# RGB_LED_Shett.net
KiCad netlist of a schematic drawn in Altium Designer
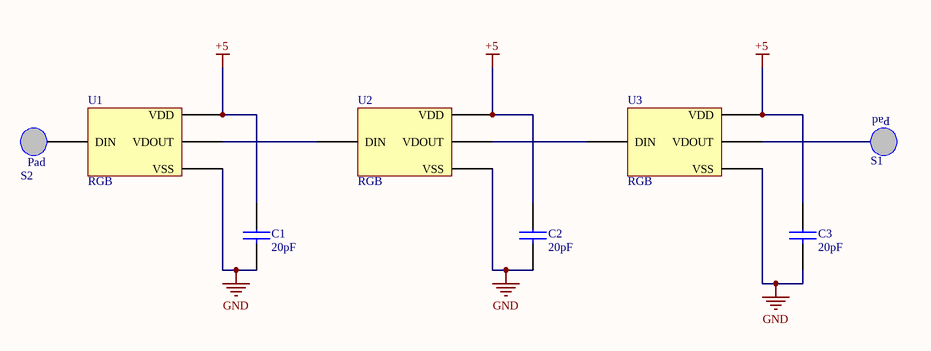
[diagram p0: RGB LED Shett.SchDoc]

(export (version "E")
  (design (tool "Eeschema 10.0.6"))
  (components
    (comp (ref "C1")
      (value "CL10C200JB8NNNC")
      (footprint "CAP_0603")
      (description "CAP CER 20pF %5 0603 SMD")
      (fields
        (field (name "MANUFACTURER") "Samsung")
        (field (name "TOLERANCE") "5%")
        (field (name "CAPACITANCE") "20pF")
        (field (name "DESIGNED BY") "BERK")
      )
      (libsource (lib "Integrated_Library01") (part "CAP CER 20pF 0603"))
    )
    (comp (ref "C2")
      (value "CL10C200JB8NNNC")
      (footprint "CAP_0603")
      (description "CAP CER 20pF %5 0603 SMD")
      (fields
        (field (name "MANUFACTURER") "Samsung")
        (field (name "TOLERANCE") "5%")
        (field (name "CAPACITANCE") "20pF")
        (field (name "DESIGNED BY") "BERK")
      )
      (libsource (lib "Integrated_Library01") (part "CAP CER 20pF 0603"))
    )
    (comp (ref "C3")
      (value "CL10C200JB8NNNC")
      (footprint "CAP_0603")
      (description "CAP CER 20pF %5 0603 SMD")
      (fields
        (field (name "MANUFACTURER") "Samsung")
        (field (name "TOLERANCE") "5%")
        (field (name "CAPACITANCE") "20pF")
        (field (name "DESIGNED BY") "BERK")
      )
      (libsource (lib "Integrated_Library01") (part "CAP CER 20pF 0603"))
    )
    (comp (ref "S1")
      (value "RGBsolderpad")
      (footprint "Solderpad0")
      (description "SOLDER PAD")
      (libsource (lib "Integrated_Library01") (part "RGBsolderpad"))
    )
    (comp (ref "S2")
      (value "RGBsolderpad")
      (footprint "Solderpad0")
      (description "SOLDER PAD")
      (libsource (lib "Integrated_Library01") (part "RGBsolderpad"))
    )
    (comp (ref "U1")
      (value "RGB")
      (footprint "RGB LED 1655")
      (description "Neopixel 5050 RGB LED with Integrated Driver Chip - 10 Pack")
      (fields
        (field (name "MANUFACTURER") "Adafruit Industries")
        (field (name "MANUFACTURER PART NUMBER") "1655")
      )
      (libsource (lib "Integrated_Library01") (part "RGB LED 1655"))
    )
    (comp (ref "U2")
      (value "RGB")
      (footprint "RGB LED 1655")
      (description "Neopixel 5050 RGB LED with Integrated Driver Chip - 10 Pack")
      (fields
        (field (name "MANUFACTURER") "Adafruit Industries")
        (field (name "MANUFACTURER PART NUMBER") "1655")
      )
      (libsource (lib "Integrated_Library01") (part "RGB LED 1655"))
    )
    (comp (ref "U3")
      (value "RGB")
      (footprint "RGB LED 1655")
      (description "Neopixel 5050 RGB LED with Integrated Driver Chip - 10 Pack")
      (fields
        (field (name "MANUFACTURER") "Adafruit Industries")
        (field (name "MANUFACTURER PART NUMBER") "1655")
      )
      (libsource (lib "Integrated_Library01") (part "RGB LED 1655"))
    )
  )
  (nets
    (net (code "1") (name "+5") (class "Default")
      (node (ref "C1") (pin "1") (pinfunction "1_1") (pintype "passive"))
      (node (ref "C2") (pin "1") (pinfunction "1_1") (pintype "passive"))
      (node (ref "C3") (pin "1") (pinfunction "1_1") (pintype "passive"))
      (node (ref "U1") (pin "2") (pinfunction "VDD_2") (pintype "passive"))
      (node (ref "U2") (pin "2") (pinfunction "VDD_2") (pintype "passive"))
      (node (ref "U3") (pin "2") (pinfunction "VDD_2") (pintype "passive"))
    )
    (net (code "2") (name "GND") (class "Default")
      (node (ref "C1") (pin "2") (pinfunction "2_2") (pintype "passive"))
      (node (ref "C2") (pin "2") (pinfunction "2_2") (pintype "passive"))
      (node (ref "C3") (pin "2") (pinfunction "2_2") (pintype "passive"))
      (node (ref "U1") (pin "4") (pinfunction "VSS_4") (pintype "passive"))
      (node (ref "U2") (pin "4") (pinfunction "VSS_4") (pintype "passive"))
      (node (ref "U3") (pin "4") (pinfunction "VSS_4") (pintype "passive"))
    )
    (net (code "3") (name "Net-(U1-DIN)") (class "Default")
      (node (ref "S2") (pin "1") (pintype "passive"))
      (node (ref "U1") (pin "1") (pinfunction "DIN_1") (pintype "passive"))
    )
    (net (code "4") (name "Net-(U1-VDOUT)") (class "Default")
      (node (ref "U1") (pin "3") (pinfunction "VDOUT_3") (pintype "passive"))
      (node (ref "U2") (pin "1") (pinfunction "DIN_1") (pintype "passive"))
    )
    (net (code "5") (name "Net-(U2-VDOUT)") (class "Default")
      (node (ref "U2") (pin "3") (pinfunction "VDOUT_3") (pintype "passive"))
      (node (ref "U3") (pin "1") (pinfunction "DIN_1") (pintype "passive"))
    )
    (net (code "6") (name "Net-(U3-VDOUT)") (class "Default")
      (node (ref "S1") (pin "1") (pintype "passive"))
      (node (ref "U3") (pin "3") (pinfunction "VDOUT_3") (pintype "passive"))
    )
  )
)
